# Sheet2.net
KiCad netlist of a schematic drawn in Altium Designer
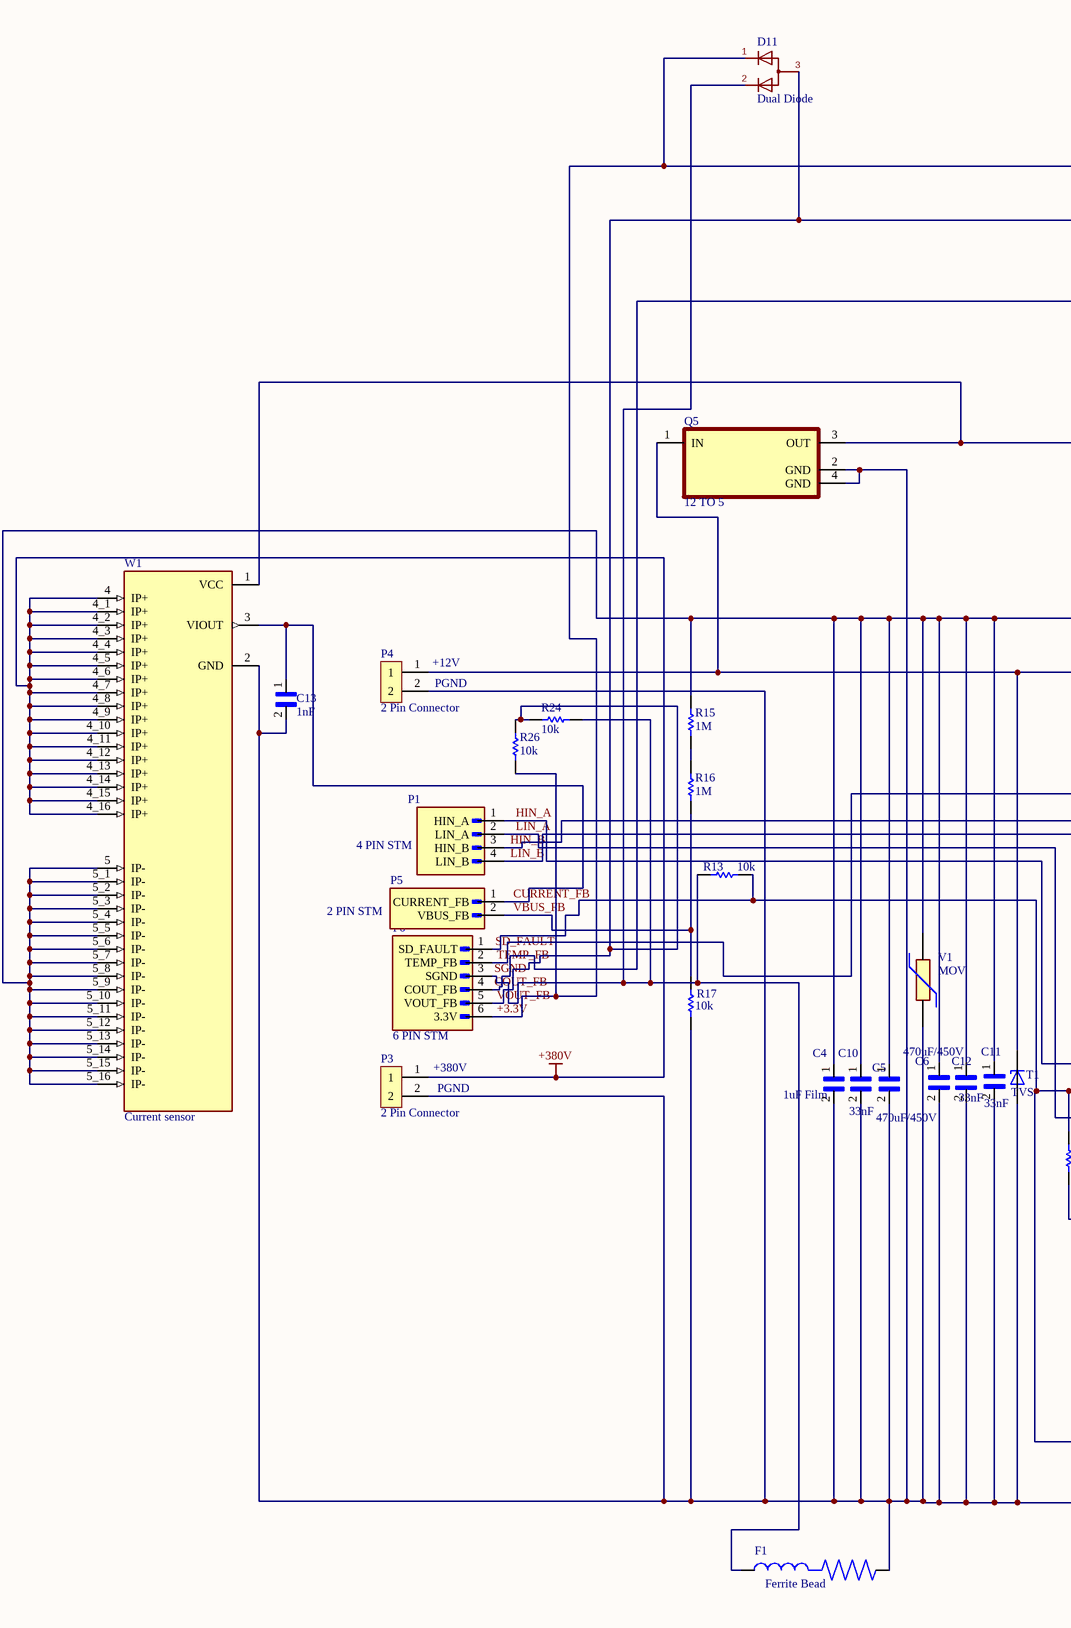
[diagram p0: Sheet2.SchDoc, left]
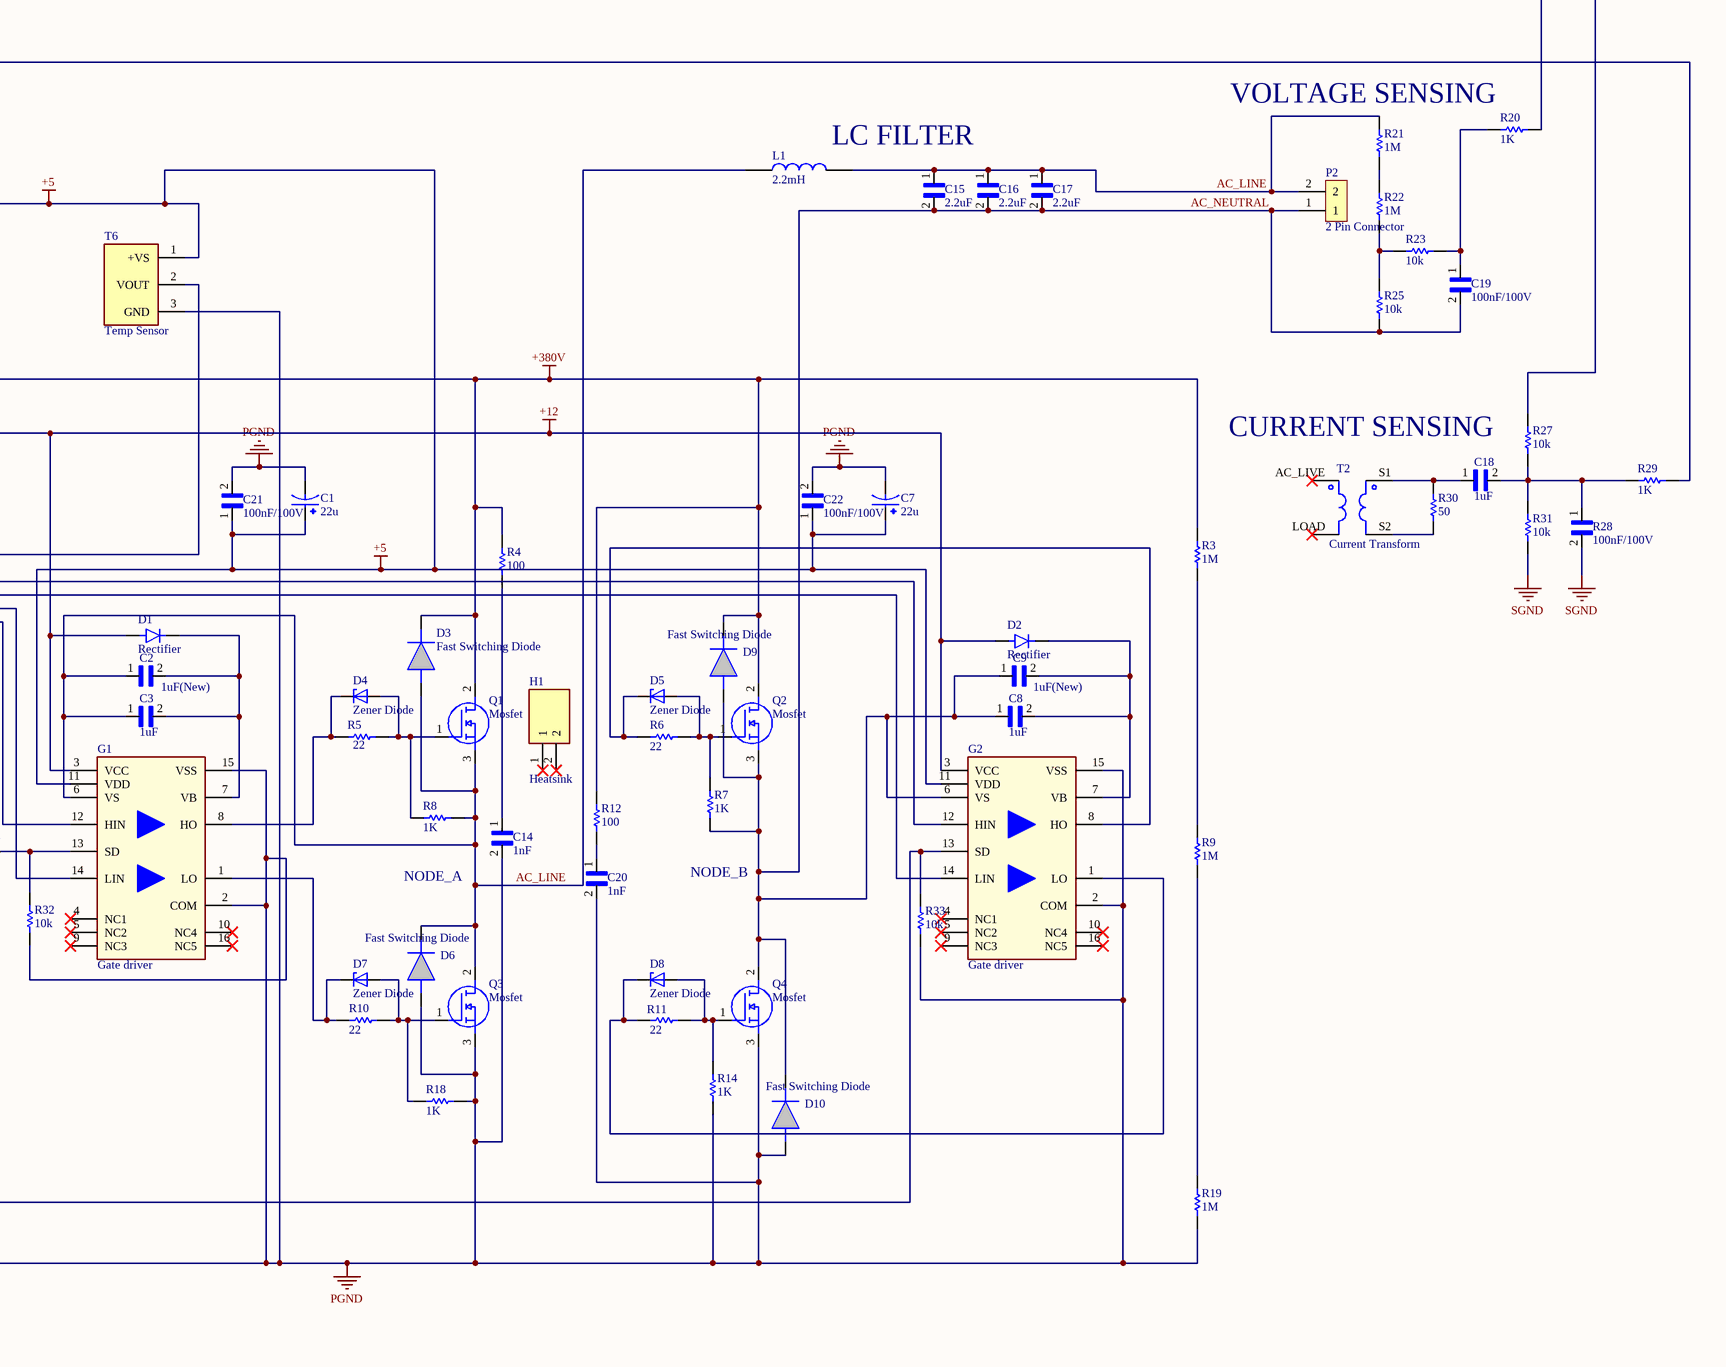
[diagram p1: Sheet2.SchDoc, right]

(export (version "E")
  (design (tool "Eeschema 10.0.6"))
  (components
    (comp (ref "C1")
      (value "22u")
      (footprint "22uF")
      (description "EEU-FR1H220")
      (libsource (lib "Schlib2") (part "22u"))
    )
    (comp (ref "C2")
      (value "1uF(New)")
      (footprint "1uF(New)")
      (description "CL21B105MBFNNNE")
      (libsource (lib "Schlib2") (part "1uF(New)"))
    )
    (comp (ref "C3")
      (value "1uF")
      (footprint "1uF")
      (description "C1206C105K1RACTU")
      (libsource (lib "Schlib2") (part "1uF"))
    )
    (comp (ref "C4")
      (value "1uF Film")
      (footprint "1.0uF/630V")
      (description "ECW-FE2J105QD")
      (libsource (lib "Schlib2") (part "1uF Film"))
    )
    (comp (ref "C5")
      (value "470uF/450V")
      (footprint "470 µF/450 V")
      (description "ELG477M450AT6AA")
      (libsource (lib "Schlib2") (part "470uF/450V"))
    )
    (comp (ref "C6")
      (value "470uF/450V")
      (footprint "470 µF/450 V")
      (description "ELG477M450AT6AA")
      (libsource (lib "Schlib2") (part "470uF/450V"))
    )
    (comp (ref "C7")
      (value "22u")
      (footprint "22uF")
      (description "EEU-FR1H220")
      (libsource (lib "Schlib2") (part "22u"))
    )
    (comp (ref "C8")
      (value "1uF")
      (footprint "1uF")
      (description "C1206C105K1RACTU")
      (libsource (lib "Schlib2") (part "1uF"))
    )
    (comp (ref "C9")
      (value "1uF(New)")
      (footprint "1uF(New)")
      (description "CL21B105MBFNNNE")
      (libsource (lib "Schlib2") (part "1uF(New)"))
    )
    (comp (ref "C10")
      (value "33nF")
      (footprint "33nF")
      (description "ECW-FD2J333JB")
      (libsource (lib "Schlib2") (part "33nF"))
    )
    (comp (ref "C11")
      (value "33nF")
      (footprint "33nF")
      (description "ECW-FD2J333JB")
      (libsource (lib "Schlib2") (part "33nF"))
    )
    (comp (ref "C12")
      (value "33nF")
      (footprint "33nF")
      (description "ECW-FD2J333JB")
      (libsource (lib "Schlib2") (part "33nF"))
    )
    (comp (ref "C13")
      (value "1nF")
      (footprint "1nF")
      (description "C315C102KAG5TA")
      (libsource (lib "Schlib2") (part "1nF"))
    )
    (comp (ref "C14")
      (value "1nF")
      (footprint "1nF")
      (description "C315C102KAG5TA")
      (libsource (lib "Schlib2") (part "1nF"))
    )
    (comp (ref "C15")
      (value "2.2uF")
      (footprint "2.2uF")
      (description "ECWFE2W225KA")
      (libsource (lib "Schlib2") (part "2.2uF"))
    )
    (comp (ref "C16")
      (value "2.2uF")
      (footprint "2.2uF")
      (description "ECWFE2W225KA")
      (libsource (lib "Schlib2") (part "2.2uF"))
    )
    (comp (ref "C17")
      (value "2.2uF")
      (footprint "2.2uF")
      (description "ECWFE2W225KA")
      (libsource (lib "Schlib2") (part "2.2uF"))
    )
    (comp (ref "C18")
      (value "1uF")
      (footprint "1uF")
      (description "C1206C105K1RACTU")
      (libsource (lib "Schlib2") (part "1uF"))
    )
    (comp (ref "C19")
      (value "100nF/100V")
      (footprint "100nF/100V")
      (description "C1210C104K1RACAUTO")
      (libsource (lib "") (part "100nF/100V_1"))
    )
    (comp (ref "C20")
      (value "1nF")
      (footprint "1nF")
      (description "C315C102KAG5TA")
      (libsource (lib "Schlib2") (part "1nF"))
    )
    (comp (ref "C21")
      (value "100nF/100V")
      (footprint "100nF/100V")
      (description "C1210C104K1RACAUTO")
      (libsource (lib "Schlib2") (part "100nF/100V"))
    )
    (comp (ref "C22")
      (value "100nF/100V")
      (footprint "100nF/100V")
      (description "C1210C104K1RACAUTO")
      (libsource (lib "Schlib2") (part "100nF/100V"))
    )
    (comp (ref "D1")
      (value "Rectifier")
      (footprint "Rectifier")
      (description "MUR160G")
      (libsource (lib "Schlib2") (part "Rectifier"))
    )
    (comp (ref "D2")
      (value "Rectifier")
      (footprint "Rectifier")
      (description "MUR160G")
      (libsource (lib "Schlib2") (part "Rectifier"))
    )
    (comp (ref "D3")
      (value "Fast Switching Diode")
      (footprint "Fast Switching Diode")
      (description "1N4148W-7-F")
      (libsource (lib "Schlib2") (part "Fast Switching Diode"))
    )
    (comp (ref "D4")
      (value "Zener Diode")
      (footprint "Zener Diode")
      (description "BZT52C18")
      (libsource (lib "Schlib2") (part "Zener Diode"))
    )
    (comp (ref "D5")
      (value "Zener Diode")
      (footprint "Zener Diode")
      (description "BZT52C18")
      (libsource (lib "Schlib2") (part "Zener Diode"))
    )
    (comp (ref "D6")
      (value "Fast Switching Diode")
      (footprint "Fast Switching Diode")
      (description "1N4148W-7-F")
      (libsource (lib "Schlib2") (part "Fast Switching Diode"))
    )
    (comp (ref "D7")
      (value "Zener Diode")
      (footprint "Zener Diode")
      (description "BZT52C18")
      (libsource (lib "Schlib2") (part "Zener Diode"))
    )
    (comp (ref "D8")
      (value "Zener Diode")
      (footprint "Zener Diode")
      (description "BZT52C18")
      (libsource (lib "Schlib2") (part "Zener Diode"))
    )
    (comp (ref "D9")
      (value "Fast Switching Diode")
      (footprint "Fast Switching Diode")
      (description "1N4148W-7-F")
      (libsource (lib "Schlib2") (part "Fast Switching Diode"))
    )
    (comp (ref "D10")
      (value "Fast Switching Diode")
      (footprint "Fast Switching Diode")
      (description "1N4148W-7-F")
      (libsource (lib "Schlib2") (part "Fast Switching Diode"))
    )
    (comp (ref "D11")
      (value "Dual Diode")
      (footprint "Dual Diode")
      (description "BAT54C")
      (libsource (lib "Schlib2") (part "Dual Diode"))
    )
    (comp (ref "F1")
      (value "Ferrite Bead")
      (footprint "Ferrite Bead")
      (description "BLM21PG221SN1D")
      (libsource (lib "Schlib2") (part "Ferrite Bead"))
    )
    (comp (ref "G1")
      (value "Gate driver")
      (footprint "Gate Driver")
      (description "IR2110")
      (libsource (lib "Schlib2") (part "Gate driver"))
    )
    (comp (ref "G2")
      (value "Gate driver")
      (footprint "Gate Driver")
      (description "IR2110")
      (libsource (lib "Schlib2") (part "Gate driver"))
    )
    (comp (ref "H1")
      (value "Heatsink")
      (footprint "Heatsink")
      (description "694-100")
      (libsource (lib "Schlib2") (part "Heatsink"))
    )
    (comp (ref "L1")
      (value "2.2mH")
      (footprint "2.2mH")
      (description "RLB0914-222KL")
      (libsource (lib "Schlib2") (part "2.2mH"))
    )
    (comp (ref "P1")
      (value "4 PIN STM")
      (footprint "4 PIN STM")
      (description "M20-9990446")
      (libsource (lib "Schlib2") (part "4 PIN STM"))
    )
    (comp (ref "P2")
      (value "2 Pin Connector")
      (footprint "2 Pin Connector")
      (description "KF301-2P")
      (libsource (lib "") (part "2 Pin Connector_1"))
    )
    (comp (ref "P3")
      (value "2 Pin Connector")
      (footprint "2 Pin Connector")
      (description "KF301-2P")
      (libsource (lib "Schlib2") (part "2 Pin Connector"))
    )
    (comp (ref "P4")
      (value "2 Pin Connector")
      (footprint "2 Pin Connector")
      (description "KF301-2P")
      (libsource (lib "Schlib2") (part "2 Pin Connector"))
    )
    (comp (ref "P5")
      (value "2 PIN STM")
      (footprint "2 PIN STM")
      (description "M20-9990246")
      (libsource (lib "Schlib2") (part "2 PIN STM"))
    )
    (comp (ref "P6")
      (value "6 PIN STM")
      (footprint "6 PIN STM")
      (description "M20-9990646")
      (libsource (lib "Schlib2") (part "6 PIN STM"))
    )
    (comp (ref "Q1")
      (value "Mosfet")
      (footprint "Mosfet")
      (description "STW69N65M5")
      (libsource (lib "Schlib2") (part "Mosfet"))
    )
    (comp (ref "Q2")
      (value "Mosfet")
      (footprint "Mosfet")
      (description "STW69N65M5")
      (libsource (lib "Schlib2") (part "Mosfet"))
    )
    (comp (ref "Q3")
      (value "Mosfet")
      (footprint "Mosfet")
      (description "STW69N65M5")
      (libsource (lib "Schlib2") (part "Mosfet"))
    )
    (comp (ref "Q4")
      (value "Mosfet")
      (footprint "Mosfet")
      (description "STW69N65M5")
      (libsource (lib "Schlib2") (part "Mosfet"))
    )
    (comp (ref "Q5")
      (value "12 TO 5")
      (footprint "12 TO 5")
      (description "LM7805S")
      (libsource (lib "Schlib2") (part "12 TO 5"))
    )
    (comp (ref "R3")
      (value "1M")
      (footprint "1M")
      (description "PTF651M0000BYEA")
      (libsource (lib "Schlib2") (part "1M"))
    )
    (comp (ref "R4")
      (value "100")
      (footprint "100")
      (description "CFR-25JB-52-100R")
      (libsource (lib "Schlib2") (part "100"))
    )
    (comp (ref "R5")
      (value "22")
      (footprint "22")
      (description "CFR-25JR-52-22R")
      (libsource (lib "Schlib2") (part "22"))
    )
    (comp (ref "R6")
      (value "22")
      (footprint "22")
      (description "CFR-25JR-52-22R")
      (libsource (lib "Schlib2") (part "22"))
    )
    (comp (ref "R7")
      (value "1K")
      (footprint "1K")
      (description "MF0207FRE52-1K")
      (libsource (lib "Schlib2") (part "1K"))
    )
    (comp (ref "R8")
      (value "1K")
      (footprint "1K")
      (description "MF0207FRE52-1K")
      (libsource (lib "Schlib2") (part "1K"))
    )
    (comp (ref "R9")
      (value "1M")
      (footprint "1M")
      (description "PTF651M0000BYEA")
      (libsource (lib "Schlib2") (part "1M"))
    )
    (comp (ref "R10")
      (value "22")
      (footprint "22")
      (description "CFR-25JR-52-22R")
      (libsource (lib "Schlib2") (part "22"))
    )
    (comp (ref "R11")
      (value "22")
      (footprint "22")
      (description "CFR-25JR-52-22R")
      (libsource (lib "Schlib2") (part "22"))
    )
    (comp (ref "R12")
      (value "100")
      (footprint "100")
      (description "CFR-25JB-52-100R")
      (libsource (lib "Schlib2") (part "100"))
    )
    (comp (ref "R13")
      (value "10k")
      (footprint "10K")
      (description "RC1206FR-0710KL")
      (libsource (lib "Schlib2") (part "10k"))
    )
    (comp (ref "R14")
      (value "1K")
      (footprint "1K")
      (description "MF0207FRE52-1K")
      (libsource (lib "Schlib2") (part "1K"))
    )
    (comp (ref "R15")
      (value "1M")
      (footprint "1M")
      (description "PTF651M0000BYEA")
      (libsource (lib "Schlib2") (part "1M"))
    )
    (comp (ref "R16")
      (value "1M")
      (footprint "1M")
      (description "PTF651M0000BYEA")
      (libsource (lib "Schlib2") (part "1M"))
    )
    (comp (ref "R17")
      (value "10k")
      (footprint "10K")
      (description "RC1206FR-0710KL")
      (libsource (lib "Schlib2") (part "10k"))
    )
    (comp (ref "R18")
      (value "1K")
      (footprint "1K")
      (description "MF0207FRE52-1K")
      (libsource (lib "Schlib2") (part "1K"))
    )
    (comp (ref "R19")
      (value "1M")
      (footprint "1M")
      (description "PTF651M0000BYEA")
      (libsource (lib "Schlib2") (part "1M"))
    )
    (comp (ref "R20")
      (value "1K")
      (footprint "1K")
      (description "MF0207FRE52-1K")
      (libsource (lib "Schlib2") (part "1K"))
    )
    (comp (ref "R21")
      (value "1M")
      (footprint "1M")
      (description "PTF651M0000BYEA")
      (libsource (lib "Schlib2") (part "1M"))
    )
    (comp (ref "R22")
      (value "1M")
      (footprint "1M")
      (description "PTF651M0000BYEA")
      (libsource (lib "Schlib2") (part "1M"))
    )
    (comp (ref "R23")
      (value "10k")
      (footprint "10K")
      (description "RC1206FR-0710KL")
      (libsource (lib "Schlib2") (part "10k"))
    )
    (comp (ref "R24")
      (value "10k")
      (footprint "10K")
      (description "RC1206FR-0710KL")
      (libsource (lib "Schlib2") (part "10k"))
    )
    (comp (ref "R25")
      (value "10k")
      (footprint "10K")
      (description "RC1206FR-0710KL")
      (libsource (lib "Schlib2") (part "10k"))
    )
    (comp (ref "R26")
      (value "10k")
      (footprint "10K")
      (description "RC1206FR-0710KL")
      (libsource (lib "Schlib2") (part "10k"))
    )
    (comp (ref "R27")
      (value "10k")
      (footprint "10K")
      (description "RC1206FR-0710KL")
      (libsource (lib "Schlib2") (part "10k"))
    )
    (comp (ref "R28")
      (value "100nF/100V")
      (footprint "100nF/100V")
      (description "C1210C104K1RACAUTO")
      (libsource (lib "") (part "100nF/100V_1"))
    )
    (comp (ref "R29")
      (value "1K")
      (footprint "1K")
      (description "MF0207FRE52-1K")
      (libsource (lib "Schlib2") (part "1K"))
    )
    (comp (ref "R30")
      (value "50")
      (footprint "50")
      (description "MF0207FTE52-49R9")
      (libsource (lib "Schlib2") (part "50"))
    )
    (comp (ref "R31")
      (value "10k")
      (footprint "10K")
      (description "RC1206FR-0710KL")
      (libsource (lib "Schlib2") (part "10k"))
    )
    (comp (ref "R32")
      (value "10k")
      (footprint "10K")
      (description "RC1206FR-0710KL")
      (libsource (lib "Schlib2") (part "10k"))
    )
    (comp (ref "R33")
      (value "10k")
      (footprint "10K")
      (description "RC1206FR-0710KL")
      (libsource (lib "Schlib2") (part "10k"))
    )
    (comp (ref "T1")
      (value "TVS")
      (footprint "TVS")
      (description "SMAJ15A")
      (libsource (lib "Schlib2") (part "TVS"))
    )
    (comp (ref "T2")
      (value "Current Transform")
      (footprint "Current Transformer")
      (description "ZMCT103C")
      (libsource (lib "Schlib2") (part "Current Transform"))
    )
    (comp (ref "T6")
      (value "Temp Sensor")
      (footprint "Temp Sensor")
      (description "LM35DZ")
      (libsource (lib "Schlib2") (part "Temp Sensor"))
    )
    (comp (ref "V1")
      (value "MOV")
      (footprint "MOV")
      (description "B72220S0421K101")
      (libsource (lib "Schlib2") (part "MOV"))
    )
    (comp (ref "W1")
      (value "Current sensor")
      (footprint "Current Sensor")
      (description "ACS758LCB-050B-PFF-T")
      (libsource (lib "Schlib2") (part "Current sensor"))
    )
  )
  (nets
    (net (code "1") (name "+5") (class "Default")
      (node (ref "C1") (pin "P") (pinfunction "P_P") (pintype "passive"))
      (node (ref "C21") (pin "1") (pinfunction "1_1") (pintype "passive"))
      (node (ref "C22") (pin "1") (pinfunction "1_1") (pintype "passive"))
      (node (ref "C7") (pin "P") (pinfunction "P_P") (pintype "passive"))
      (node (ref "G1") (pin "11") (pinfunction "VDD_11") (pintype "power_in"))
      (node (ref "G2") (pin "11") (pinfunction "VDD_11") (pintype "power_in"))
      (node (ref "Q5") (pin "3") (pinfunction "OUT_3") (pintype "passive"))
      (node (ref "T6") (pin "1") (pinfunction "+VS_1") (pintype "power_in"))
      (node (ref "W1") (pin "1") (pinfunction "VCC_1") (pintype "power_in"))
    )
    (net (code "2") (name "+12") (class "Default")
      (node (ref "D1") (pin "1") (pinfunction "1_1") (pintype "passive"))
      (node (ref "D2") (pin "1") (pinfunction "1_1") (pintype "passive"))
      (node (ref "G1") (pin "3") (pinfunction "VCC_3") (pintype "power_in"))
      (node (ref "G2") (pin "3") (pinfunction "VCC_3") (pintype "power_in"))
      (node (ref "P4") (pin "1") (pinfunction "1_1") (pintype "passive"))
      (node (ref "Q5") (pin "1") (pinfunction "IN_1") (pintype "passive"))
      (node (ref "T1") (pin "C") (pinfunction "C_C") (pintype "passive"))
    )
    (net (code "3") (name "+380V") (class "Default")
      (node (ref "C10") (pin "1") (pinfunction "1_1") (pintype "passive"))
      (node (ref "C11") (pin "1") (pinfunction "1_1") (pintype "passive"))
      (node (ref "C12") (pin "1") (pinfunction "1_1") (pintype "passive"))
      (node (ref "C4") (pin "1") (pinfunction "1_1") (pintype "passive"))
      (node (ref "C5") (pin "1") (pinfunction "1_1") (pintype "passive"))
      (node (ref "C6") (pin "1") (pinfunction "1_1") (pintype "passive"))
      (node (ref "D3") (pin "1") (pinfunction "K_1") (pintype "passive"))
      (node (ref "D9") (pin "1") (pinfunction "K_1") (pintype "passive"))
      (node (ref "P3") (pin "1") (pinfunction "1_1") (pintype "passive"))
      (node (ref "Q1") (pin "2") (pinfunction "D_2") (pintype "passive"))
      (node (ref "Q2") (pin "2") (pinfunction "D_2") (pintype "passive"))
      (node (ref "R12") (pin "2") (pinfunction "2_2") (pintype "passive"))
      (node (ref "R15") (pin "2") (pinfunction "2_2") (pintype "passive"))
      (node (ref "R3") (pin "2") (pinfunction "2_2") (pintype "passive"))
      (node (ref "R4") (pin "2") (pinfunction "2_2") (pintype "passive"))
      (node (ref "V1") (pin "2") (pinfunction "2_2") (pintype "passive"))
      (node (ref "W1") (pin "4") (pinfunction "IP+_4") (pintype "input"))
      (node (ref "W1") (pin "4_1") (pinfunction "IP+_4_1") (pintype "input"))
      (node (ref "W1") (pin "4_10") (pinfunction "IP+_4_10") (pintype "input"))
      (node (ref "W1") (pin "4_11") (pinfunction "IP+_4_11") (pintype "input"))
      (node (ref "W1") (pin "4_12") (pinfunction "IP+_4_12") (pintype "input"))
      (node (ref "W1") (pin "4_13") (pinfunction "IP+_4_13") (pintype "input"))
      (node (ref "W1") (pin "4_14") (pinfunction "IP+_4_14") (pintype "input"))
      (node (ref "W1") (pin "4_15") (pinfunction "IP+_4_15") (pintype "input"))
      (node (ref "W1") (pin "4_16") (pinfunction "IP+_4_16") (pintype "input"))
      (node (ref "W1") (pin "4_2") (pinfunction "IP+_4_2") (pintype "input"))
      (node (ref "W1") (pin "4_3") (pinfunction "IP+_4_3") (pintype "input"))
      (node (ref "W1") (pin "4_4") (pinfunction "IP+_4_4") (pintype "input"))
      (node (ref "W1") (pin "4_5") (pinfunction "IP+_4_5") (pintype "input"))
      (node (ref "W1") (pin "4_6") (pinfunction "IP+_4_6") (pintype "input"))
      (node (ref "W1") (pin "4_7") (pinfunction "IP+_4_7") (pintype "input"))
      (node (ref "W1") (pin "4_8") (pinfunction "IP+_4_8") (pintype "input"))
      (node (ref "W1") (pin "4_9") (pinfunction "IP+_4_9") (pintype "input"))
      (node (ref "W1") (pin "5") (pinfunction "IP-_5") (pintype "input"))
      (node (ref "W1") (pin "5_1") (pinfunction "IP-_5_1") (pintype "input"))
      (node (ref "W1") (pin "5_10") (pinfunction "IP-_5_10") (pintype "input"))
      (node (ref "W1") (pin "5_11") (pinfunction "IP-_5_11") (pintype "input"))
      (node (ref "W1") (pin "5_12") (pinfunction "IP-_5_12") (pintype "input"))
      (node (ref "W1") (pin "5_13") (pinfunction "IP-_5_13") (pintype "input"))
      (node (ref "W1") (pin "5_14") (pinfunction "IP-_5_14") (pintype "input"))
      (node (ref "W1") (pin "5_15") (pinfunction "IP-_5_15") (pintype "input"))
      (node (ref "W1") (pin "5_16") (pinfunction "IP-_5_16") (pintype "input"))
      (node (ref "W1") (pin "5_2") (pinfunction "IP-_5_2") (pintype "input"))
      (node (ref "W1") (pin "5_3") (pinfunction "IP-_5_3") (pintype "input"))
      (node (ref "W1") (pin "5_4") (pinfunction "IP-_5_4") (pintype "input"))
      (node (ref "W1") (pin "5_5") (pinfunction "IP-_5_5") (pintype "input"))
      (node (ref "W1") (pin "5_6") (pinfunction "IP-_5_6") (pintype "input"))
      (node (ref "W1") (pin "5_7") (pinfunction "IP-_5_7") (pintype "input"))
      (node (ref "W1") (pin "5_8") (pinfunction "IP-_5_8") (pintype "input"))
      (node (ref "W1") (pin "5_9") (pinfunction "IP-_5_9") (pintype "input"))
    )
    (net (code "4") (name "/+3.3V") (class "Default")
      (node (ref "D11") (pin "1") (pinfunction "C_1") (pintype "passive"))
      (node (ref "P6") (pin "6") (pinfunction "3.3V_6") (pintype "passive"))
      (node (ref "R26") (pin "1") (pinfunction "1_1") (pintype "passive"))
      (node (ref "R27") (pin "2") (pinfunction "2_2") (pintype "passive"))
    )
    (net (code "5") (name "/AC_LINE") (class "Default")
      (node (ref "C15") (pin "1") (pinfunction "1_1") (pintype "passive"))
      (node (ref "C16") (pin "1") (pinfunction "1_1") (pintype "passive"))
      (node (ref "C17") (pin "1") (pinfunction "1_1") (pintype "passive"))
      (node (ref "C2") (pin "1") (pinfunction "1_1") (pintype "passive"))
      (node (ref "C3") (pin "1") (pinfunction "1_1") (pintype "passive"))
      (node (ref "D3") (pin "2") (pinfunction "A_2") (pintype "passive"))
      (node (ref "D6") (pin "1") (pinfunction "K_1") (pintype "passive"))
      (node (ref "G1") (pin "6") (pinfunction "VS_6") (pintype "power_in"))
      (node (ref "L1") (pin "1") (pinfunction "1_1") (pintype "passive"))
      (node (ref "L1") (pin "2") (pinfunction "2_2") (pintype "passive"))
      (node (ref "P2") (pin "2") (pinfunction "2_2") (pintype "passive"))
      (node (ref "Q1") (pin "3") (pinfunction "S_3") (pintype "passive"))
      (node (ref "Q3") (pin "2") (pinfunction "D_2") (pintype "passive"))
      (node (ref "R21") (pin "2") (pinfunction "2_2") (pintype "passive"))
      (node (ref "R8") (pin "2") (pinfunction "2_2") (pintype "passive"))
    )
    (net (code "6") (name "/AC_NEUTRAL") (class "Default")
      (node (ref "C15") (pin "2") (pinfunction "2_2") (pintype "passive"))
      (node (ref "C16") (pin "2") (pinfunction "2_2") (pintype "passive"))
      (node (ref "C17") (pin "2") (pinfunction "2_2") (pintype "passive"))
      (node (ref "C19") (pin "2") (pinfunction "2_2") (pintype "passive"))
      (node (ref "C8") (pin "1") (pinfunction "1_1") (pintype "passive"))
      (node (ref "C9") (pin "1") (pinfunction "1_1") (pintype "passive"))
      (node (ref "D10") (pin "1") (pinfunction "K_1") (pintype "passive"))
      (node (ref "D9") (pin "2") (pinfunction "A_2") (pintype "passive"))
      (node (ref "G2") (pin "6") (pinfunction "VS_6") (pintype "power_in"))
      (node (ref "P2") (pin "1") (pinfunction "1_1") (pintype "passive"))
      (node (ref "Q2") (pin "3") (pinfunction "S_3") (pintype "passive"))
      (node (ref "Q4") (pin "2") (pinfunction "D_2") (pintype "passive"))
      (node (ref "R25") (pin "1") (pinfunction "1_1") (pintype "passive"))
      (node (ref "R7") (pin "1") (pinfunction "1_1") (pintype "passive"))
    )
    (net (code "7") (name "/COUT_FB") (class "Default")
      (node (ref "P6") (pin "4") (pinfunction "COUT_FB_4") (pintype "passive"))
      (node (ref "R29") (pin "2") (pinfunction "2_2") (pintype "passive"))
    )
    (net (code "8") (name "/CURRENT_FB") (class "Default")
      (node (ref "C13") (pin "1") (pinfunction "1_1") (pintype "passive"))
      (node (ref "P5") (pin "1") (pinfunction "CURRENT_FB_1") (pintype "passive"))
      (node (ref "W1") (pin "3") (pinfunction "VIOUT_3") (pintype "output"))
    )
    (net (code "9") (name "/HIN_A") (class "Default")
      (node (ref "G1") (pin "12") (pinfunction "HIN_12") (pintype "passive"))
      (node (ref "P1") (pin "1") (pinfunction "HIN_A_1") (pintype "passive"))
    )
    (net (code "10") (name "/HIN_B") (class "Default")
      (node (ref "G2") (pin "12") (pinfunction "HIN_12") (pintype "passive"))
      (node (ref "P1") (pin "3") (pinfunction "HIN_B_3") (pintype "passive"))
    )
    (net (code "11") (name "/LIN_A") (class "Default")
      (node (ref "G1") (pin "14") (pinfunction "LIN_14") (pintype "passive"))
      (node (ref "P1") (pin "2") (pinfunction "LIN_A_2") (pintype "passive"))
    )
    (net (code "12") (name "/LIN_B") (class "Default")
      (node (ref "G2") (pin "14") (pinfunction "LIN_14") (pintype "passive"))
      (node (ref "P1") (pin "4") (pinfunction "LIN_B_4") (pintype "passive"))
    )
    (net (code "13") (name "/SD_FAULT") (class "Default")
      (node (ref "G1") (pin "13") (pinfunction "SD_13") (pintype "passive"))
      (node (ref "G2") (pin "13") (pinfunction "SD_13") (pintype "passive"))
      (node (ref "P6") (pin "1") (pinfunction "SD_FAULT_1") (pintype "passive"))
      (node (ref "R13") (pin "2") (pinfunction "2_2") (pintype "passive"))
      (node (ref "R32") (pin "2") (pinfunction "2_2") (pintype "passive"))
      (node (ref "R33") (pin "2") (pinfunction "2_2") (pintype "passive"))
    )
    (net (code "14") (name "/TEMP_FB") (class "Default")
      (node (ref "P6") (pin "2") (pinfunction "TEMP_FB_2") (pintype "passive"))
      (node (ref "T6") (pin "2") (pinfunction "VOUT_2") (pintype "passive"))
    )
    (net (code "15") (name "/VBUS_FB") (class "Default")
      (node (ref "P5") (pin "2") (pinfunction "VBUS_FB_2") (pintype "passive"))
      (node (ref "R16") (pin "1") (pinfunction "1_1") (pintype "passive"))
      (node (ref "R17") (pin "2") (pinfunction "2_2") (pintype "passive"))
    )
    (net (code "16") (name "/VOUT_FB") (class "Default")
      (node (ref "D11") (pin "3") (pinfunction "A_3") (pintype "passive"))
      (node (ref "P6") (pin "5") (pinfunction "VOUT_FB_5") (pintype "passive"))
      (node (ref "R20") (pin "2") (pinfunction "2_2") (pintype "passive"))
      (node (ref "R24") (pin "2") (pinfunction "2_2") (pintype "passive"))
      (node (ref "R26") (pin "2") (pinfunction "2_2") (pintype "passive"))
    )
    (net (code "17") (name "Net-(C14-Pad1)") (class "Default")
      (node (ref "C14") (pin "1") (pinfunction "1_1") (pintype "passive"))
      (node (ref "R4") (pin "1") (pinfunction "1_1") (pintype "passive"))
    )
    (net (code "18") (name "Net-(C18-Pad2)") (class "Default")
      (node (ref "C18") (pin "2") (pinfunction "2_2") (pintype "passive"))
      (node (ref "R27") (pin "1") (pinfunction "1_1") (pintype "passive"))
      (node (ref "R28") (pin "1") (pinfunction "1_1") (pintype "passive"))
      (node (ref "R29") (pin "1") (pinfunction "1_1") (pintype "passive"))
      (node (ref "R31") (pin "2") (pinfunction "2_2") (pintype "passive"))
    )
    (net (code "19") (name "Net-(C19-Pad1)") (class "Default")
      (node (ref "C19") (pin "1") (pinfunction "1_1") (pintype "passive"))
      (node (ref "R20") (pin "1") (pinfunction "1_1") (pintype "passive"))
      (node (ref "R23") (pin "1") (pinfunction "1_1") (pintype "passive"))
    )
    (net (code "20") (name "Net-(C20-Pad1)") (class "Default")
      (node (ref "C20") (pin "1") (pinfunction "1_1") (pintype "passive"))
      (node (ref "R12") (pin "1") (pinfunction "1_1") (pintype "passive"))
    )
    (net (code "21") (name "Net-(D4-A)") (class "Default")
      (node (ref "D4") (pin "2") (pinfunction "A_2") (pintype "passive"))
      (node (ref "Q1") (pin "1") (pinfunction "G_1") (pintype "passive"))
      (node (ref "R5") (pin "2") (pinfunction "2_2") (pintype "passive"))
      (node (ref "R8") (pin "1") (pinfunction "1_1") (pintype "passive"))
    )
    (net (code "22") (name "Net-(D4-K)") (class "Default")
      (node (ref "D4") (pin "1") (pinfunction "K_1") (pintype "passive"))
      (node (ref "G1") (pin "8") (pinfunction "HO_8") (pintype "passive"))
      (node (ref "R5") (pin "1") (pinfunction "1_1") (pintype "passive"))
    )
    (net (code "23") (name "Net-(D5-A)") (class "Default")
      (node (ref "D5") (pin "2") (pinfunction "A_2") (pintype "passive"))
      (node (ref "Q2") (pin "1") (pinfunction "G_1") (pintype "passive"))
      (node (ref "R6") (pin "2") (pinfunction "2_2") (pintype "passive"))
      (node (ref "R7") (pin "2") (pinfunction "2_2") (pintype "passive"))
    )
    (net (code "24") (name "Net-(D5-K)") (class "Default")
      (node (ref "D5") (pin "1") (pinfunction "K_1") (pintype "passive"))
      (node (ref "G2") (pin "8") (pinfunction "HO_8") (pintype "passive"))
      (node (ref "R6") (pin "1") (pinfunction "1_1") (pintype "passive"))
    )
    (net (code "25") (name "Net-(D7-A)") (class "Default")
      (node (ref "D7") (pin "2") (pinfunction "A_2") (pintype "passive"))
      (node (ref "Q3") (pin "1") (pinfunction "G_1") (pintype "passive"))
      (node (ref "R10") (pin "2") (pinfunction "2_2") (pintype "passive"))
      (node (ref "R18") (pin "1") (pinfunction "1_1") (pintype "passive"))
    )
    (net (code "26") (name "Net-(D7-K)") (class "Default")
      (node (ref "D7") (pin "1") (pinfunction "K_1") (pintype "passive"))
      (node (ref "G1") (pin "1") (pinfunction "LO_1") (pintype "passive"))
      (node (ref "R10") (pin "1") (pinfunction "1_1") (pintype "passive"))
    )
    (net (code "27") (name "Net-(D8-A)") (class "Default")
      (node (ref "D8") (pin "2") (pinfunction "A_2") (pintype "passive"))
      (node (ref "Q4") (pin "1") (pinfunction "G_1") (pintype "passive"))
      (node (ref "R11") (pin "2") (pinfunction "2_2") (pintype "passive"))
      (node (ref "R14") (pin "2") (pinfunction "2_2") (pintype "passive"))
    )
    (net (code "28") (name "Net-(D8-K)") (class "Default")
      (node (ref "D8") (pin "1") (pinfunction "K_1") (pintype "passive"))
      (node (ref "G2") (pin "1") (pinfunction "LO_1") (pintype "passive"))
      (node (ref "R11") (pin "1") (pinfunction "1_1") (pintype "passive"))
    )
    (net (code "29") (name "Net-(G1-VB)") (class "Default")
      (node (ref "C2") (pin "2") (pinfunction "2_2") (pintype "passive"))
      (node (ref "C3") (pin "2") (pinfunction "2_2") (pintype "passive"))
      (node (ref "D1") (pin "2") (pinfunction "2_2") (pintype "passive"))
      (node (ref "G1") (pin "7") (pinfunction "VB_7") (pintype "power_in"))
    )
    (net (code "30") (name "Net-(G2-VB)") (class "Default")
      (node (ref "C8") (pin "2") (pinfunction "2_2") (pintype "passive"))
      (node (ref "C9") (pin "2") (pinfunction "2_2") (pintype "passive"))
      (node (ref "D2") (pin "2") (pinfunction "2_2") (pintype "passive"))
      (node (ref "G2") (pin "7") (pinfunction "VB_7") (pintype "power_in"))
    )
    (net (code "31") (name "Net-(R3-Pad1)") (class "Default")
      (node (ref "R3") (pin "1") (pinfunction "1_1") (pintype "passive"))
      (node (ref "R9") (pin "2") (pinfunction "2_2") (pintype "passive"))
    )
    (net (code "32") (name "Net-(R15-Pad1)") (class "Default")
      (node (ref "R15") (pin "1") (pinfunction "1_1") (pintype "passive"))
      (node (ref "R16") (pin "2") (pinfunction "2_2") (pintype "passive"))
    )
    (net (code "33") (name "Net-(R19-Pad2)") (class "Default")
      (node (ref "R19") (pin "2") (pinfunction "2_2") (pintype "passive"))
      (node (ref "R9") (pin "1") (pinfunction "1_1") (pintype "passive"))
    )
    (net (code "34") (name "Net-(R21-Pad1)") (class "Default")
      (node (ref "R21") (pin "1") (pinfunction "1_1") (pintype "passive"))
      (node (ref "R22") (pin "2") (pinfunction "2_2") (pintype "passive"))
    )
    (net (code "35") (name "Net-(R22-Pad1)") (class "Default")
      (node (ref "R22") (pin "1") (pinfunction "1_1") (pintype "passive"))
      (node (ref "R23") (pin "2") (pinfunction "2_2") (pintype "passive"))
      (node (ref "R25") (pin "2") (pinfunction "2_2") (pintype "passive"))
    )
    (net (code "36") (name "Net-(T2-5)") (class "Default")
      (node (ref "R30") (pin "1") (pinfunction "1_1") (pintype "passive"))
      (node (ref "T2") (pin "S2") (pinfunction "5_S2") (pintype "passive"))
    )
    (net (code "37") (name "Net-(T2-8)") (class "Default")
      (node (ref "C18") (pin "1") (pinfunction "1_1") (pintype "passive"))
      (node (ref "R30") (pin "2") (pinfunction "2_2") (pintype "passive"))
      (node (ref "T2") (pin "S1") (pinfunction "8_S1") (pintype "passive"))
    )
    (net (code "38") (name "PGND") (class "Default")
      (node (ref "C1") (pin "N") (pinfunction "N_N") (pintype "passive"))
      (node (ref "C10") (pin "2") (pinfunction "2_2") (pintype "passive"))
      (node (ref "C11") (pin "2") (pinfunction "2_2") (pintype "passive"))
      (node (ref "C12") (pin "2") (pinfunction "2_2") (pintype "passive"))
      (node (ref "C13") (pin "2") (pinfunction "2_2") (pintype "passive"))
      (node (ref "C14") (pin "2") (pinfunction "2_2") (pintype "passive"))
      (node (ref "C20") (pin "2") (pinfunction "2_2") (pintype "passive"))
      (node (ref "C21") (pin "2") (pinfunction "2_2") (pintype "passive"))
      (node (ref "C22") (pin "2") (pinfunction "2_2") (pintype "passive"))
      (node (ref "C4") (pin "2") (pinfunction "2_2") (pintype "passive"))
      (node (ref "C5") (pin "2") (pinfunction "2_2") (pintype "passive"))
      (node (ref "C6") (pin "2") (pinfunction "2_2") (pintype "passive"))
      (node (ref "C7") (pin "N") (pinfunction "N_N") (pintype "passive"))
      (node (ref "D10") (pin "2") (pinfunction "A_2") (pintype "passive"))
      (node (ref "D6") (pin "2") (pinfunction "A_2") (pintype "passive"))
      (node (ref "F1") (pin "2") (pinfunction "2_2") (pintype "passive"))
      (node (ref "G1") (pin "15") (pinfunction "VSS_15") (pintype "power_in"))
      (node (ref "G1") (pin "2") (pinfunction "COM_2") (pintype "power_in"))
      (node (ref "G2") (pin "15") (pinfunction "VSS_15") (pintype "power_in"))
      (node (ref "G2") (pin "2") (pinfunction "COM_2") (pintype "power_in"))
      (node (ref "P3") (pin "2") (pinfunction "2_2") (pintype "passive"))
      (node (ref "P4") (pin "2") (pinfunction "2_2") (pintype "passive"))
      (node (ref "Q3") (pin "3") (pinfunction "S_3") (pintype "passive"))
      (node (ref "Q4") (pin "3") (pinfunction "S_3") (pintype "passive"))
      (node (ref "Q5") (pin "2") (pinfunction "GND_2") (pintype "power_in"))
      (node (ref "Q5") (pin "4") (pinfunction "GND_4") (pintype "power_in"))
      (node (ref "R14") (pin "1") (pinfunction "1_1") (pintype "passive"))
      (node (ref "R17") (pin "1") (pinfunction "1_1") (pintype "passive"))
      (node (ref "R18") (pin "2") (pinfunction "2_2") (pintype "passive"))
      (node (ref "R19") (pin "1") (pinfunction "1_1") (pintype "passive"))
      (node (ref "R32") (pin "1") (pinfunction "1_1") (pintype "passive"))
      (node (ref "R33") (pin "1") (pinfunction "1_1") (pintype "passive"))
      (node (ref "T1") (pin "A") (pinfunction "A_A") (pintype "passive"))
      (node (ref "T6") (pin "3") (pinfunction "GND_3") (pintype "power_in"))
      (node (ref "V1") (pin "1") (pinfunction "1_1") (pintype "passive"))
      (node (ref "W1") (pin "2") (pinfunction "GND_2") (pintype "power_in"))
    )
    (net (code "39") (name "SGND") (class "Default")
      (node (ref "D11") (pin "2") (pinfunction "C_2") (pintype "passive"))
      (node (ref "F1") (pin "1") (pinfunction "1_1") (pintype "passive"))
      (node (ref "P6") (pin "3") (pinfunction "SGND_3") (pintype "passive"))
      (node (ref "R13") (pin "1") (pinfunction "1_1") (pintype "passive"))
      (node (ref "R24") (pin "1") (pinfunction "1_1") (pintype "passive"))
      (node (ref "R28") (pin "2") (pinfunction "2_2") (pintype "passive"))
      (node (ref "R31") (pin "1") (pinfunction "1_1") (pintype "passive"))
    )
    (net (code "40") (name "unconnected-(G1-NC1-Pad4)") (class "Default")
      (node (ref "G1") (pin "4") (pinfunction "NC1_4") (pintype "passive+no_connect"))
    )
    (net (code "41") (name "unconnected-(G1-NC2-Pad5)") (class "Default")
      (node (ref "G1") (pin "5") (pinfunction "NC2_5") (pintype "passive+no_connect"))
    )
    (net (code "42") (name "unconnected-(G1-NC3-Pad9)") (class "Default")
      (node (ref "G1") (pin "9") (pinfunction "NC3_9") (pintype "passive+no_connect"))
    )
    (net (code "43") (name "unconnected-(G1-NC4-Pad10)") (class "Default")
      (node (ref "G1") (pin "10") (pinfunction "NC4_10") (pintype "passive+no_connect"))
    )
    (net (code "44") (name "unconnected-(G1-NC5-Pad16)") (class "Default")
      (node (ref "G1") (pin "16") (pinfunction "NC5_16") (pintype "passive+no_connect"))
    )
    (net (code "45") (name "unconnected-(G2-NC1-Pad4)") (class "Default")
      (node (ref "G2") (pin "4") (pinfunction "NC1_4") (pintype "passive+no_connect"))
    )
    (net (code "46") (name "unconnected-(G2-NC2-Pad5)") (class "Default")
      (node (ref "G2") (pin "5") (pinfunction "NC2_5") (pintype "passive+no_connect"))
    )
    (net (code "47") (name "unconnected-(G2-NC3-Pad9)") (class "Default")
      (node (ref "G2") (pin "9") (pinfunction "NC3_9") (pintype "passive+no_connect"))
    )
    (net (code "48") (name "unconnected-(G2-NC4-Pad10)") (class "Default")
      (node (ref "G2") (pin "10") (pinfunction "NC4_10") (pintype "passive+no_connect"))
    )
    (net (code "49") (name "unconnected-(G2-NC5-Pad16)") (class "Default")
      (node (ref "G2") (pin "16") (pinfunction "NC5_16") (pintype "passive+no_connect"))
    )
    (net (code "50") (name "unconnected-(H1-Pad1)") (class "Default")
      (node (ref "H1") (pin "1") (pinfunction "1_1") (pintype "passive+no_connect"))
    )
    (net (code "51") (name "unconnected-(H1-Pad2)") (class "Default")
      (node (ref "H1") (pin "2") (pinfunction "2_2") (pintype "passive+no_connect"))
    )
    (net (code "52") (name "unconnected-(T2-1A-PadLOAD)") (class "Default")
      (node (ref "T2") (pin "LOAD") (pinfunction "1A_LOAD") (pintype "passive+no_connect"))
    )
    (net (code "53") (name "unconnected-(T2-2A-PadAC_LIVE)") (class "Default")
      (node (ref "T2") (pin "AC_LIVE") (pinfunction "2A_AC_LIVE") (pintype "passive+no_connect"))
    )
  )
)
